# S_A_jumper_bed.net
KiCad netlist of a schematic drawn in EAGLE
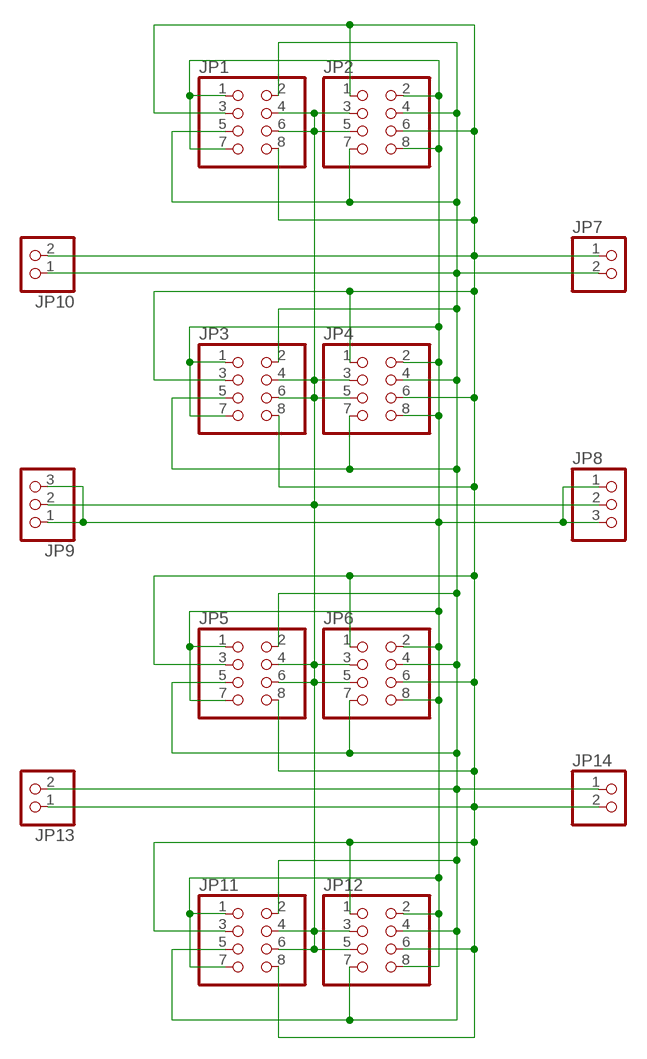
[diagram p0: schematic, sheet 1]

(export (version "E")
  (design (tool "Eeschema 10.0.6"))
  (components
    (comp (ref "JP1")
      (value "PINHD-2X4")
      (footprint "eagle-import:2X04")
      (libsource (lib "eagle-import") (part "PINHD-2X4"))
    )
    (comp (ref "JP2")
      (value "PINHD-2X4")
      (footprint "eagle-import:2X04")
      (libsource (lib "eagle-import") (part "PINHD-2X4"))
    )
    (comp (ref "JP3")
      (value "PINHD-2X4")
      (footprint "eagle-import:2X04")
      (libsource (lib "eagle-import") (part "PINHD-2X4"))
    )
    (comp (ref "JP4")
      (value "PINHD-2X4")
      (footprint "eagle-import:2X04")
      (libsource (lib "eagle-import") (part "PINHD-2X4"))
    )
    (comp (ref "JP5")
      (value "PINHD-2X4")
      (footprint "eagle-import:2X04")
      (libsource (lib "eagle-import") (part "PINHD-2X4"))
    )
    (comp (ref "JP6")
      (value "PINHD-2X4")
      (footprint "eagle-import:2X04")
      (libsource (lib "eagle-import") (part "PINHD-2X4"))
    )
    (comp (ref "JP7")
      (value "PINHD-1X2/90")
      (footprint "eagle-import:1X02_90")
      (libsource (lib "eagle-import") (part "PINHD-1X2/90"))
    )
    (comp (ref "JP8")
      (value "PINHD-1X3/90")
      (footprint "eagle-import:1X03_90")
      (libsource (lib "eagle-import") (part "PINHD-1X3/90"))
    )
    (comp (ref "JP9")
      (value "PINHD-1X31X03/90F")
      (footprint "eagle-import:1X03_90F")
      (libsource (lib "eagle-import") (part "PINHD-1X31X03/90F"))
    )
    (comp (ref "JP10")
      (value "PINHD-1X21X02/90F")
      (footprint "eagle-import:1X02_90F")
      (libsource (lib "eagle-import") (part "PINHD-1X21X02/90F"))
    )
    (comp (ref "JP11")
      (value "PINHD-2X4")
      (footprint "eagle-import:2X04")
      (libsource (lib "eagle-import") (part "PINHD-2X4"))
    )
    (comp (ref "JP12")
      (value "PINHD-2X4")
      (footprint "eagle-import:2X04")
      (libsource (lib "eagle-import") (part "PINHD-2X4"))
    )
    (comp (ref "JP13")
      (value "PINHD-1X21X02/90F")
      (footprint "eagle-import:1X02_90F")
      (libsource (lib "eagle-import") (part "PINHD-1X21X02/90F"))
    )
    (comp (ref "JP14")
      (value "PINHD-1X2/90")
      (footprint "eagle-import:1X02_90")
      (libsource (lib "eagle-import") (part "PINHD-1X2/90"))
    )
  )
  (nets
    (net (code "1") (name "Net-(JP1-Pad1)") (class "Default")
      (node (ref "JP1") (pin "1") (pinfunction "1_1") (pintype "passive"))
      (node (ref "JP1") (pin "7") (pinfunction "7_7") (pintype "passive"))
      (node (ref "JP11") (pin "1") (pinfunction "1_1") (pintype "passive"))
      (node (ref "JP11") (pin "7") (pinfunction "7_7") (pintype "passive"))
      (node (ref "JP12") (pin "2") (pinfunction "2_2") (pintype "passive"))
      (node (ref "JP12") (pin "8") (pinfunction "8_8") (pintype "passive"))
      (node (ref "JP2") (pin "2") (pinfunction "2_2") (pintype "passive"))
      (node (ref "JP2") (pin "8") (pinfunction "8_8") (pintype "passive"))
      (node (ref "JP3") (pin "1") (pinfunction "1_1") (pintype "passive"))
      (node (ref "JP3") (pin "7") (pinfunction "7_7") (pintype "passive"))
      (node (ref "JP4") (pin "2") (pinfunction "2_2") (pintype "passive"))
      (node (ref "JP4") (pin "8") (pinfunction "8_8") (pintype "passive"))
      (node (ref "JP5") (pin "1") (pinfunction "1_1") (pintype "passive"))
      (node (ref "JP5") (pin "7") (pinfunction "7_7") (pintype "passive"))
      (node (ref "JP6") (pin "2") (pinfunction "2_2") (pintype "passive"))
      (node (ref "JP6") (pin "8") (pinfunction "8_8") (pintype "passive"))
      (node (ref "JP8") (pin "1") (pinfunction "1_1") (pintype "passive"))
      (node (ref "JP8") (pin "3") (pinfunction "3_3") (pintype "passive"))
      (node (ref "JP9") (pin "1") (pinfunction "1_1") (pintype "passive"))
      (node (ref "JP9") (pin "3") (pinfunction "3_3") (pintype "passive"))
    )
    (net (code "2") (name "Net-(JP1-Pad2)") (class "Default")
      (node (ref "JP1") (pin "2") (pinfunction "2_2") (pintype "passive"))
      (node (ref "JP1") (pin "5") (pinfunction "5_5") (pintype "passive"))
      (node (ref "JP10") (pin "1") (pinfunction "1_1") (pintype "passive"))
      (node (ref "JP11") (pin "2") (pinfunction "2_2") (pintype "passive"))
      (node (ref "JP11") (pin "5") (pinfunction "5_5") (pintype "passive"))
      (node (ref "JP12") (pin "4") (pinfunction "4_4") (pintype "passive"))
      (node (ref "JP12") (pin "7") (pinfunction "7_7") (pintype "passive"))
      (node (ref "JP13") (pin "2") (pinfunction "2_2") (pintype "passive"))
      (node (ref "JP14") (pin "1") (pinfunction "1_1") (pintype "passive"))
      (node (ref "JP2") (pin "4") (pinfunction "4_4") (pintype "passive"))
      (node (ref "JP2") (pin "7") (pinfunction "7_7") (pintype "passive"))
      (node (ref "JP3") (pin "2") (pinfunction "2_2") (pintype "passive"))
      (node (ref "JP3") (pin "5") (pinfunction "5_5") (pintype "passive"))
      (node (ref "JP4") (pin "4") (pinfunction "4_4") (pintype "passive"))
      (node (ref "JP4") (pin "7") (pinfunction "7_7") (pintype "passive"))
      (node (ref "JP5") (pin "2") (pinfunction "2_2") (pintype "passive"))
      (node (ref "JP5") (pin "5") (pinfunction "5_5") (pintype "passive"))
      (node (ref "JP6") (pin "4") (pinfunction "4_4") (pintype "passive"))
      (node (ref "JP6") (pin "7") (pinfunction "7_7") (pintype "passive"))
      (node (ref "JP7") (pin "2") (pinfunction "2_2") (pintype "passive"))
    )
    (net (code "3") (name "Net-(JP1-Pad3)") (class "Default")
      (node (ref "JP1") (pin "3") (pinfunction "3_3") (pintype "passive"))
      (node (ref "JP1") (pin "8") (pinfunction "8_8") (pintype "passive"))
      (node (ref "JP10") (pin "2") (pinfunction "2_2") (pintype "passive"))
      (node (ref "JP11") (pin "3") (pinfunction "3_3") (pintype "passive"))
      (node (ref "JP11") (pin "8") (pinfunction "8_8") (pintype "passive"))
      (node (ref "JP12") (pin "1") (pinfunction "1_1") (pintype "passive"))
      (node (ref "JP12") (pin "6") (pinfunction "6_6") (pintype "passive"))
      (node (ref "JP13") (pin "1") (pinfunction "1_1") (pintype "passive"))
      (node (ref "JP14") (pin "2") (pinfunction "2_2") (pintype "passive"))
      (node (ref "JP2") (pin "1") (pinfunction "1_1") (pintype "passive"))
      (node (ref "JP2") (pin "6") (pinfunction "6_6") (pintype "passive"))
      (node (ref "JP3") (pin "3") (pinfunction "3_3") (pintype "passive"))
      (node (ref "JP3") (pin "8") (pinfunction "8_8") (pintype "passive"))
      (node (ref "JP4") (pin "1") (pinfunction "1_1") (pintype "passive"))
      (node (ref "JP4") (pin "6") (pinfunction "6_6") (pintype "passive"))
      (node (ref "JP5") (pin "3") (pinfunction "3_3") (pintype "passive"))
      (node (ref "JP5") (pin "8") (pinfunction "8_8") (pintype "passive"))
      (node (ref "JP6") (pin "1") (pinfunction "1_1") (pintype "passive"))
      (node (ref "JP6") (pin "6") (pinfunction "6_6") (pintype "passive"))
      (node (ref "JP7") (pin "1") (pinfunction "1_1") (pintype "passive"))
    )
    (net (code "4") (name "Net-(JP1-Pad4)") (class "Default")
      (node (ref "JP1") (pin "4") (pinfunction "4_4") (pintype "passive"))
      (node (ref "JP1") (pin "6") (pinfunction "6_6") (pintype "passive"))
      (node (ref "JP11") (pin "4") (pinfunction "4_4") (pintype "passive"))
      (node (ref "JP11") (pin "6") (pinfunction "6_6") (pintype "passive"))
      (node (ref "JP12") (pin "3") (pinfunction "3_3") (pintype "passive"))
      (node (ref "JP12") (pin "5") (pinfunction "5_5") (pintype "passive"))
      (node (ref "JP2") (pin "3") (pinfunction "3_3") (pintype "passive"))
      (node (ref "JP2") (pin "5") (pinfunction "5_5") (pintype "passive"))
      (node (ref "JP3") (pin "4") (pinfunction "4_4") (pintype "passive"))
      (node (ref "JP3") (pin "6") (pinfunction "6_6") (pintype "passive"))
      (node (ref "JP4") (pin "3") (pinfunction "3_3") (pintype "passive"))
      (node (ref "JP4") (pin "5") (pinfunction "5_5") (pintype "passive"))
      (node (ref "JP5") (pin "4") (pinfunction "4_4") (pintype "passive"))
      (node (ref "JP5") (pin "6") (pinfunction "6_6") (pintype "passive"))
      (node (ref "JP6") (pin "3") (pinfunction "3_3") (pintype "passive"))
      (node (ref "JP6") (pin "5") (pinfunction "5_5") (pintype "passive"))
      (node (ref "JP8") (pin "2") (pinfunction "2_2") (pintype "passive"))
      (node (ref "JP9") (pin "2") (pinfunction "2_2") (pintype "passive"))
    )
  )
)
